# KSZ_Switch.net
KiCad netlist of a schematic drawn in Altium Designer
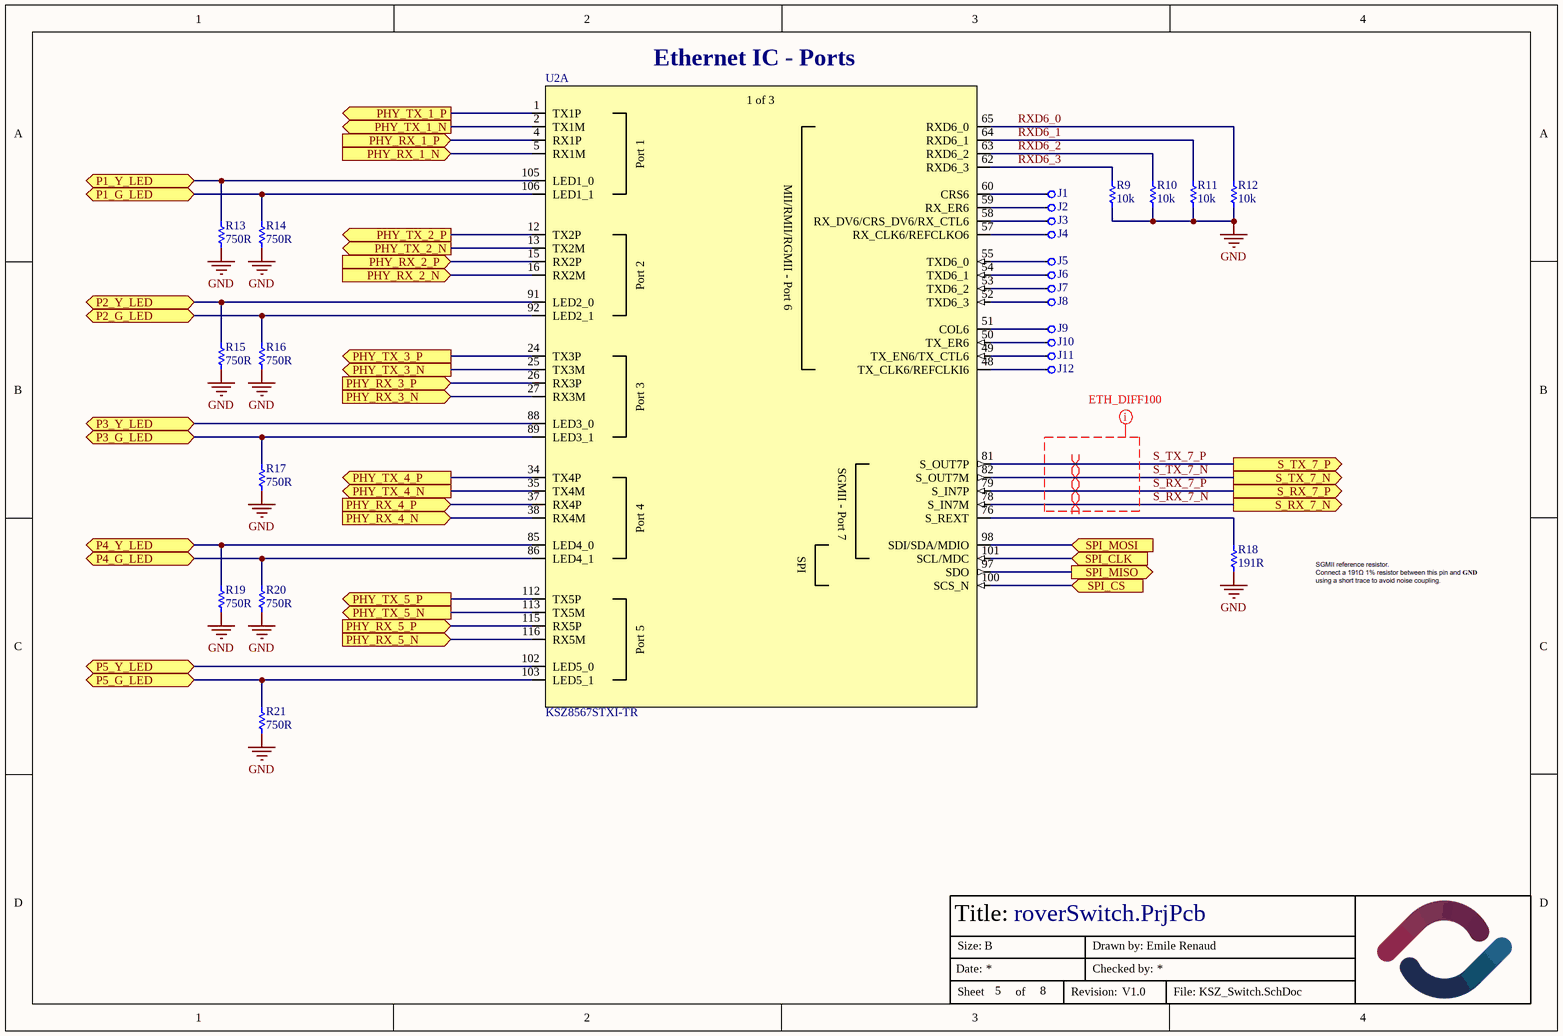
[diagram p0: KSZ_Switch.SchDoc]

(export (version "E")
  (design (tool "Eeschema 10.0.6"))
  (components
    (comp (ref "J1")
      (value "hole")
      (footprint "PCB_Footprints:PAD-0.53MM")
      (description "PAD for 28 AWG Solid Wire")
      (libsource (lib "JumpersAndHoles") (part "PAD 0.53mm AWG28-Solid"))
    )
    (comp (ref "J2")
      (value "hole")
      (footprint "PCB_Footprints:PAD-0.53MM")
      (description "PAD for 28 AWG Solid Wire")
      (libsource (lib "JumpersAndHoles") (part "PAD 0.53mm AWG28-Solid"))
    )
    (comp (ref "J3")
      (value "hole")
      (footprint "PCB_Footprints:PAD-0.53MM")
      (description "PAD for 28 AWG Solid Wire")
      (libsource (lib "JumpersAndHoles") (part "PAD 0.53mm AWG28-Solid"))
    )
    (comp (ref "J4")
      (value "hole")
      (footprint "PCB_Footprints:PAD-0.53MM")
      (description "PAD for 28 AWG Solid Wire")
      (libsource (lib "JumpersAndHoles") (part "PAD 0.53mm AWG28-Solid"))
    )
    (comp (ref "J5")
      (value "hole")
      (footprint "PCB_Footprints:PAD-0.53MM")
      (description "PAD for 28 AWG Solid Wire")
      (libsource (lib "JumpersAndHoles") (part "PAD 0.53mm AWG28-Solid"))
    )
    (comp (ref "J6")
      (value "hole")
      (footprint "PCB_Footprints:PAD-0.53MM")
      (description "PAD for 28 AWG Solid Wire")
      (libsource (lib "JumpersAndHoles") (part "PAD 0.53mm AWG28-Solid"))
    )
    (comp (ref "J7")
      (value "hole")
      (footprint "PCB_Footprints:PAD-0.53MM")
      (description "PAD for 28 AWG Solid Wire")
      (libsource (lib "JumpersAndHoles") (part "PAD 0.53mm AWG28-Solid"))
    )
    (comp (ref "J8")
      (value "hole")
      (footprint "PCB_Footprints:PAD-0.53MM")
      (description "PAD for 28 AWG Solid Wire")
      (libsource (lib "JumpersAndHoles") (part "PAD 0.53mm AWG28-Solid"))
    )
    (comp (ref "J9")
      (value "hole")
      (footprint "PCB_Footprints:PAD-0.53MM")
      (description "PAD for 28 AWG Solid Wire")
      (libsource (lib "JumpersAndHoles") (part "PAD 0.53mm AWG28-Solid"))
    )
    (comp (ref "J10")
      (value "hole")
      (footprint "PCB_Footprints:PAD-0.53MM")
      (description "PAD for 28 AWG Solid Wire")
      (libsource (lib "JumpersAndHoles") (part "PAD 0.53mm AWG28-Solid"))
    )
    (comp (ref "J11")
      (value "hole")
      (footprint "PCB_Footprints:PAD-0.53MM")
      (description "PAD for 28 AWG Solid Wire")
      (libsource (lib "JumpersAndHoles") (part "PAD 0.53mm AWG28-Solid"))
    )
    (comp (ref "J12")
      (value "hole")
      (footprint "PCB_Footprints:PAD-0.53MM")
      (description "PAD for 28 AWG Solid Wire")
      (libsource (lib "JumpersAndHoles") (part "PAD 0.53mm AWG28-Solid"))
    )
    (comp (ref "R9")
      (value "10k")
      (footprint "Resistor-0603")
      (description "Resistor0603-10k")
      (fields (field (name "Comment") "SMT resistor"))
      (libsource (lib "Resistors") (part "Resistor-0603-10k"))
    )
    (comp (ref "R10")
      (value "10k")
      (footprint "Resistor-0603")
      (description "Resistor0603-10k")
      (fields (field (name "Comment") "SMT resistor"))
      (libsource (lib "Resistors") (part "Resistor-0603-10k"))
    )
    (comp (ref "R11")
      (value "10k")
      (footprint "Resistor-0603")
      (description "Resistor0603-10k")
      (fields (field (name "Comment") "SMT resistor"))
      (libsource (lib "Resistors") (part "Resistor-0603-10k"))
    )
    (comp (ref "R12")
      (value "10k")
      (footprint "Resistor-0603")
      (description "Resistor0603-10k")
      (fields (field (name "Comment") "SMT resistor"))
      (libsource (lib "Resistors") (part "Resistor-0603-10k"))
    )
    (comp (ref "R13")
      (value "750R")
      (footprint "Resistor-0603")
      (description "Resistor0603-750R")
      (fields (field (name "Comment") "SMT resistor"))
      (libsource (lib "Resistors") (part "Resistor-0603-750R"))
    )
    (comp (ref "R14")
      (value "750R")
      (footprint "Resistor-0603")
      (description "Resistor0603-750R")
      (fields (field (name "Comment") "SMT resistor"))
      (libsource (lib "Resistors") (part "Resistor-0603-750R"))
    )
    (comp (ref "R15")
      (value "750R")
      (footprint "Resistor-0603")
      (description "Resistor0603-750R")
      (fields (field (name "Comment") "SMT resistor"))
      (libsource (lib "Resistors") (part "Resistor-0603-750R"))
    )
    (comp (ref "R16")
      (value "750R")
      (footprint "Resistor-0603")
      (description "Resistor0603-750R")
      (fields (field (name "Comment") "SMT resistor"))
      (libsource (lib "Resistors") (part "Resistor-0603-750R"))
    )
    (comp (ref "R17")
      (value "750R")
      (footprint "Resistor-0603")
      (description "Resistor0603-750R")
      (fields (field (name "Comment") "SMT resistor"))
      (libsource (lib "Resistors") (part "Resistor-0603-750R"))
    )
    (comp (ref "R18")
      (value "191R")
      (footprint "Resistor-0603")
      (description "Resistor-0603-191R")
      (fields (field (name "Comment") "SMT resistor"))
      (libsource (lib "Resistors") (part "Resistor-0603-191R"))
    )
    (comp (ref "R19")
      (value "750R")
      (footprint "Resistor-0603")
      (description "Resistor0603-750R")
      (fields (field (name "Comment") "SMT resistor"))
      (libsource (lib "Resistors") (part "Resistor-0603-750R"))
    )
    (comp (ref "R20")
      (value "750R")
      (footprint "Resistor-0603")
      (description "Resistor0603-750R")
      (fields (field (name "Comment") "SMT resistor"))
      (libsource (lib "Resistors") (part "Resistor-0603-750R"))
    )
    (comp (ref "R21")
      (value "750R")
      (footprint "Resistor-0603")
      (description "Resistor0603-750R")
      (fields (field (name "Comment") "SMT resistor"))
      (libsource (lib "Resistors") (part "Resistor-0603-750R"))
    )
    (comp (ref "U2")
      (value "KSZ8567STXI-TR")
      (footprint "TQFP128_EP_6XX_MCH-M")
      (description "IC ETHERNET SWITCH 7PORT 128TQFP")
      (libsource (lib "Ethernet") (part "KSZ8567STXI-TR"))
    )
  )
  (nets
    (net (code "1") (name "/P1_G_LED") (class "Default")
      (node (ref "R14") (pin "2") (pinfunction "2_2") (pintype "passive"))
      (node (ref "U2") (pin "106") (pinfunction "LED1_1_106") (pintype "bidirectional"))
    )
    (net (code "2") (name "/P1_Y_LED") (class "Default")
      (node (ref "R13") (pin "2") (pinfunction "2_2") (pintype "passive"))
      (node (ref "U2") (pin "105") (pinfunction "LED1_0_105") (pintype "bidirectional"))
    )
    (net (code "3") (name "/P2_G_LED") (class "Default")
      (node (ref "R16") (pin "2") (pinfunction "2_2") (pintype "passive"))
      (node (ref "U2") (pin "92") (pinfunction "LED2_1_92") (pintype "bidirectional"))
    )
    (net (code "4") (name "/P2_Y_LED") (class "Default")
      (node (ref "R15") (pin "2") (pinfunction "2_2") (pintype "passive"))
      (node (ref "U2") (pin "91") (pinfunction "LED2_0_91") (pintype "bidirectional"))
    )
    (net (code "5") (name "/P3_G_LED") (class "Default")
      (node (ref "R17") (pin "2") (pinfunction "2_2") (pintype "passive"))
      (node (ref "U2") (pin "89") (pinfunction "LED3_1_89") (pintype "bidirectional"))
    )
    (net (code "6") (name "/P3_Y_LED") (class "Default")
      (node (ref "U2") (pin "88") (pinfunction "LED3_0_88") (pintype "bidirectional"))
    )
    (net (code "7") (name "/P4_G_LED") (class "Default")
      (node (ref "R20") (pin "2") (pinfunction "2_2") (pintype "passive"))
      (node (ref "U2") (pin "86") (pinfunction "LED4_1_86") (pintype "bidirectional"))
    )
    (net (code "8") (name "/P4_Y_LED") (class "Default")
      (node (ref "R19") (pin "2") (pinfunction "2_2") (pintype "passive"))
      (node (ref "U2") (pin "85") (pinfunction "LED4_0_85") (pintype "bidirectional"))
    )
    (net (code "9") (name "/P5_G_LED") (class "Default")
      (node (ref "R21") (pin "2") (pinfunction "2_2") (pintype "passive"))
      (node (ref "U2") (pin "103") (pinfunction "LED5_1_103") (pintype "bidirectional"))
    )
    (net (code "10") (name "/P5_Y_LED") (class "Default")
      (node (ref "U2") (pin "102") (pinfunction "LED5_0_102") (pintype "bidirectional"))
    )
    (net (code "11") (name "/PHY_RX_1_N") (class "Default")
      (node (ref "U2") (pin "5") (pinfunction "RX1M_5") (pintype "passive"))
    )
    (net (code "12") (name "/PHY_RX_1_P") (class "Default")
      (node (ref "U2") (pin "4") (pinfunction "RX1P_4") (pintype "passive"))
    )
    (net (code "13") (name "/PHY_RX_2_N") (class "Default")
      (node (ref "U2") (pin "16") (pinfunction "RX2M_16") (pintype "passive"))
    )
    (net (code "14") (name "/PHY_RX_2_P") (class "Default")
      (node (ref "U2") (pin "15") (pinfunction "RX2P_15") (pintype "passive"))
    )
    (net (code "15") (name "/PHY_RX_3_N") (class "Default")
      (node (ref "U2") (pin "27") (pinfunction "RX3M_27") (pintype "passive"))
    )
    (net (code "16") (name "/PHY_RX_3_P") (class "Default")
      (node (ref "U2") (pin "26") (pinfunction "RX3P_26") (pintype "passive"))
    )
    (net (code "17") (name "/PHY_RX_4_N") (class "Default")
      (node (ref "U2") (pin "38") (pinfunction "RX4M_38") (pintype "passive"))
    )
    (net (code "18") (name "/PHY_RX_4_P") (class "Default")
      (node (ref "U2") (pin "37") (pinfunction "RX4P_37") (pintype "passive"))
    )
    (net (code "19") (name "/PHY_RX_5_N") (class "Default")
      (node (ref "U2") (pin "116") (pinfunction "RX5M_116") (pintype "passive"))
    )
    (net (code "20") (name "/PHY_RX_5_P") (class "Default")
      (node (ref "U2") (pin "115") (pinfunction "RX5P_115") (pintype "passive"))
    )
    (net (code "21") (name "/PHY_TX_1_N") (class "Default")
      (node (ref "U2") (pin "2") (pinfunction "TX1M_2") (pintype "passive"))
    )
    (net (code "22") (name "/PHY_TX_1_P") (class "Default")
      (node (ref "U2") (pin "1") (pinfunction "TX1P_1") (pintype "passive"))
    )
    (net (code "23") (name "/PHY_TX_2_N") (class "Default")
      (node (ref "U2") (pin "13") (pinfunction "TX2M_13") (pintype "passive"))
    )
    (net (code "24") (name "/PHY_TX_2_P") (class "Default")
      (node (ref "U2") (pin "12") (pinfunction "TX2P_12") (pintype "passive"))
    )
    (net (code "25") (name "/PHY_TX_3_N") (class "Default")
      (node (ref "U2") (pin "25") (pinfunction "TX3M_25") (pintype "passive"))
    )
    (net (code "26") (name "/PHY_TX_3_P") (class "Default")
      (node (ref "U2") (pin "24") (pinfunction "TX3P_24") (pintype "passive"))
    )
    (net (code "27") (name "/PHY_TX_4_N") (class "Default")
      (node (ref "U2") (pin "35") (pinfunction "TX4M_35") (pintype "passive"))
    )
    (net (code "28") (name "/PHY_TX_4_P") (class "Default")
      (node (ref "U2") (pin "34") (pinfunction "TX4P_34") (pintype "passive"))
    )
    (net (code "29") (name "/PHY_TX_5_N") (class "Default")
      (node (ref "U2") (pin "113") (pinfunction "TX5M_113") (pintype "passive"))
    )
    (net (code "30") (name "/PHY_TX_5_P") (class "Default")
      (node (ref "U2") (pin "112") (pinfunction "TX5P_112") (pintype "passive"))
    )
    (net (code "31") (name "/RXD6_0") (class "Default")
      (node (ref "R12") (pin "2") (pinfunction "2_2") (pintype "passive"))
      (node (ref "U2") (pin "65") (pinfunction "RXD6_0_65") (pintype "bidirectional"))
    )
    (net (code "32") (name "/RXD6_1") (class "Default")
      (node (ref "R11") (pin "2") (pinfunction "2_2") (pintype "passive"))
      (node (ref "U2") (pin "64") (pinfunction "RXD6_1_64") (pintype "bidirectional"))
    )
    (net (code "33") (name "/RXD6_2") (class "Default")
      (node (ref "R10") (pin "2") (pinfunction "2_2") (pintype "passive"))
      (node (ref "U2") (pin "63") (pinfunction "RXD6_2_63") (pintype "bidirectional"))
    )
    (net (code "34") (name "/RXD6_3") (class "Default")
      (node (ref "R9") (pin "2") (pinfunction "2_2") (pintype "passive"))
      (node (ref "U2") (pin "62") (pinfunction "RXD6_3_62") (pintype "bidirectional"))
    )
    (net (code "35") (name "/SPI_CLK") (class "Default")
      (node (ref "U2") (pin "101") (pinfunction "SCL/MDC_101") (pintype "input"))
    )
    (net (code "36") (name "/SPI_CS") (class "Default")
      (node (ref "U2") (pin "100") (pinfunction "SCS_N_100") (pintype "input"))
    )
    (net (code "37") (name "/SPI_MISO") (class "Default")
      (node (ref "U2") (pin "97") (pinfunction "SDO_97") (pintype "output"))
    )
    (net (code "38") (name "/SPI_MOSI") (class "Default")
      (node (ref "U2") (pin "98") (pinfunction "SDI/SDA/MDIO_98") (pintype "bidirectional"))
    )
    (net (code "39") (name "/S_RX_7_N") (class "Default")
      (node (ref "U2") (pin "78") (pinfunction "S_IN7M_78") (pintype "input"))
    )
    (net (code "40") (name "/S_RX_7_P") (class "Default")
      (node (ref "U2") (pin "79") (pinfunction "S_IN7P_79") (pintype "input"))
    )
    (net (code "41") (name "/S_TX_7_N") (class "Default")
      (node (ref "U2") (pin "82") (pinfunction "S_OUT7M_82") (pintype "output"))
    )
    (net (code "42") (name "/S_TX_7_P") (class "Default")
      (node (ref "U2") (pin "81") (pinfunction "S_OUT7P_81") (pintype "output"))
    )
    (net (code "43") (name "GND") (class "Default")
      (node (ref "R10") (pin "1") (pinfunction "1_1") (pintype "passive"))
      (node (ref "R11") (pin "1") (pinfunction "1_1") (pintype "passive"))
      (node (ref "R12") (pin "1") (pinfunction "1_1") (pintype "passive"))
      (node (ref "R13") (pin "1") (pinfunction "1_1") (pintype "passive"))
      (node (ref "R14") (pin "1") (pinfunction "1_1") (pintype "passive"))
      (node (ref "R15") (pin "1") (pinfunction "1_1") (pintype "passive"))
      (node (ref "R16") (pin "1") (pinfunction "1_1") (pintype "passive"))
      (node (ref "R17") (pin "1") (pinfunction "1_1") (pintype "passive"))
      (node (ref "R18") (pin "1") (pinfunction "1_1") (pintype "passive"))
      (node (ref "R19") (pin "1") (pinfunction "1_1") (pintype "passive"))
      (node (ref "R20") (pin "1") (pinfunction "1_1") (pintype "passive"))
      (node (ref "R21") (pin "1") (pinfunction "1_1") (pintype "passive"))
      (node (ref "R9") (pin "1") (pinfunction "1_1") (pintype "passive"))
    )
    (net (code "44") (name "Net-(U2A-COL6)") (class "Default")
      (node (ref "J9") (pin "1") (pinfunction "1_1") (pintype "passive"))
      (node (ref "U2") (pin "51") (pinfunction "COL6_51") (pintype "bidirectional"))
    )
    (net (code "45") (name "Net-(U2A-CRS6)") (class "Default")
      (node (ref "J1") (pin "1") (pinfunction "1_1") (pintype "passive"))
      (node (ref "U2") (pin "60") (pinfunction "CRS6_60") (pintype "bidirectional"))
    )
    (net (code "46") (name "Net-(U2A-RX_CLK6{slash}REFCLKO6)") (class "Default")
      (node (ref "J4") (pin "1") (pinfunction "1_1") (pintype "passive"))
      (node (ref "U2") (pin "57") (pinfunction "RX_CLK6/REFCLKO6_57") (pintype "bidirectional"))
    )
    (net (code "47") (name "Net-(U2A-RX_DV6{slash}CRS_DV6{slash}RX_CTL6)") (class "Default")
      (node (ref "J3") (pin "1") (pinfunction "1_1") (pintype "passive"))
      (node (ref "U2") (pin "58") (pinfunction "RX_DV6/CRS_DV6/RX_CTL6_58") (pintype "bidirectional"))
    )
    (net (code "48") (name "Net-(U2A-RX_ER6)") (class "Default")
      (node (ref "J2") (pin "1") (pinfunction "1_1") (pintype "passive"))
      (node (ref "U2") (pin "59") (pinfunction "RX_ER6_59") (pintype "bidirectional"))
    )
    (net (code "49") (name "Net-(U2A-S_REXT)") (class "Default")
      (node (ref "R18") (pin "2") (pinfunction "2_2") (pintype "passive"))
      (node (ref "U2") (pin "76") (pinfunction "S_REXT_76") (pintype "passive"))
    )
    (net (code "50") (name "Net-(U2A-TXD6_0)") (class "Default")
      (node (ref "J5") (pin "1") (pinfunction "1_1") (pintype "passive"))
      (node (ref "U2") (pin "55") (pinfunction "TXD6_0_55") (pintype "input"))
    )
    (net (code "51") (name "Net-(U2A-TXD6_1)") (class "Default")
      (node (ref "J6") (pin "1") (pinfunction "1_1") (pintype "passive"))
      (node (ref "U2") (pin "54") (pinfunction "TXD6_1_54") (pintype "input"))
    )
    (net (code "52") (name "Net-(U2A-TXD6_2)") (class "Default")
      (node (ref "J7") (pin "1") (pinfunction "1_1") (pintype "passive"))
      (node (ref "U2") (pin "53") (pinfunction "TXD6_2_53") (pintype "input"))
    )
    (net (code "53") (name "Net-(U2A-TXD6_3)") (class "Default")
      (node (ref "J8") (pin "1") (pinfunction "1_1") (pintype "passive"))
      (node (ref "U2") (pin "52") (pinfunction "TXD6_3_52") (pintype "input"))
    )
    (net (code "54") (name "Net-(U2A-TX_CLK6{slash}REFCLKI6)") (class "Default")
      (node (ref "J12") (pin "1") (pinfunction "1_1") (pintype "passive"))
      (node (ref "U2") (pin "48") (pinfunction "TX_CLK6/REFCLKI6_48") (pintype "bidirectional"))
    )
    (net (code "55") (name "Net-(U2A-TX_EN6{slash}TX_CTL6)") (class "Default")
      (node (ref "J11") (pin "1") (pinfunction "1_1") (pintype "passive"))
      (node (ref "U2") (pin "49") (pinfunction "TX_EN6/TX_CTL6_49") (pintype "input"))
    )
    (net (code "56") (name "Net-(U2A-TX_ER6)") (class "Default")
      (node (ref "J10") (pin "1") (pinfunction "1_1") (pintype "passive"))
      (node (ref "U2") (pin "50") (pinfunction "TX_ER6_50") (pintype "input"))
    )
  )
)
